# 1P3W.net
KiCad netlist of a schematic drawn in EAGLE
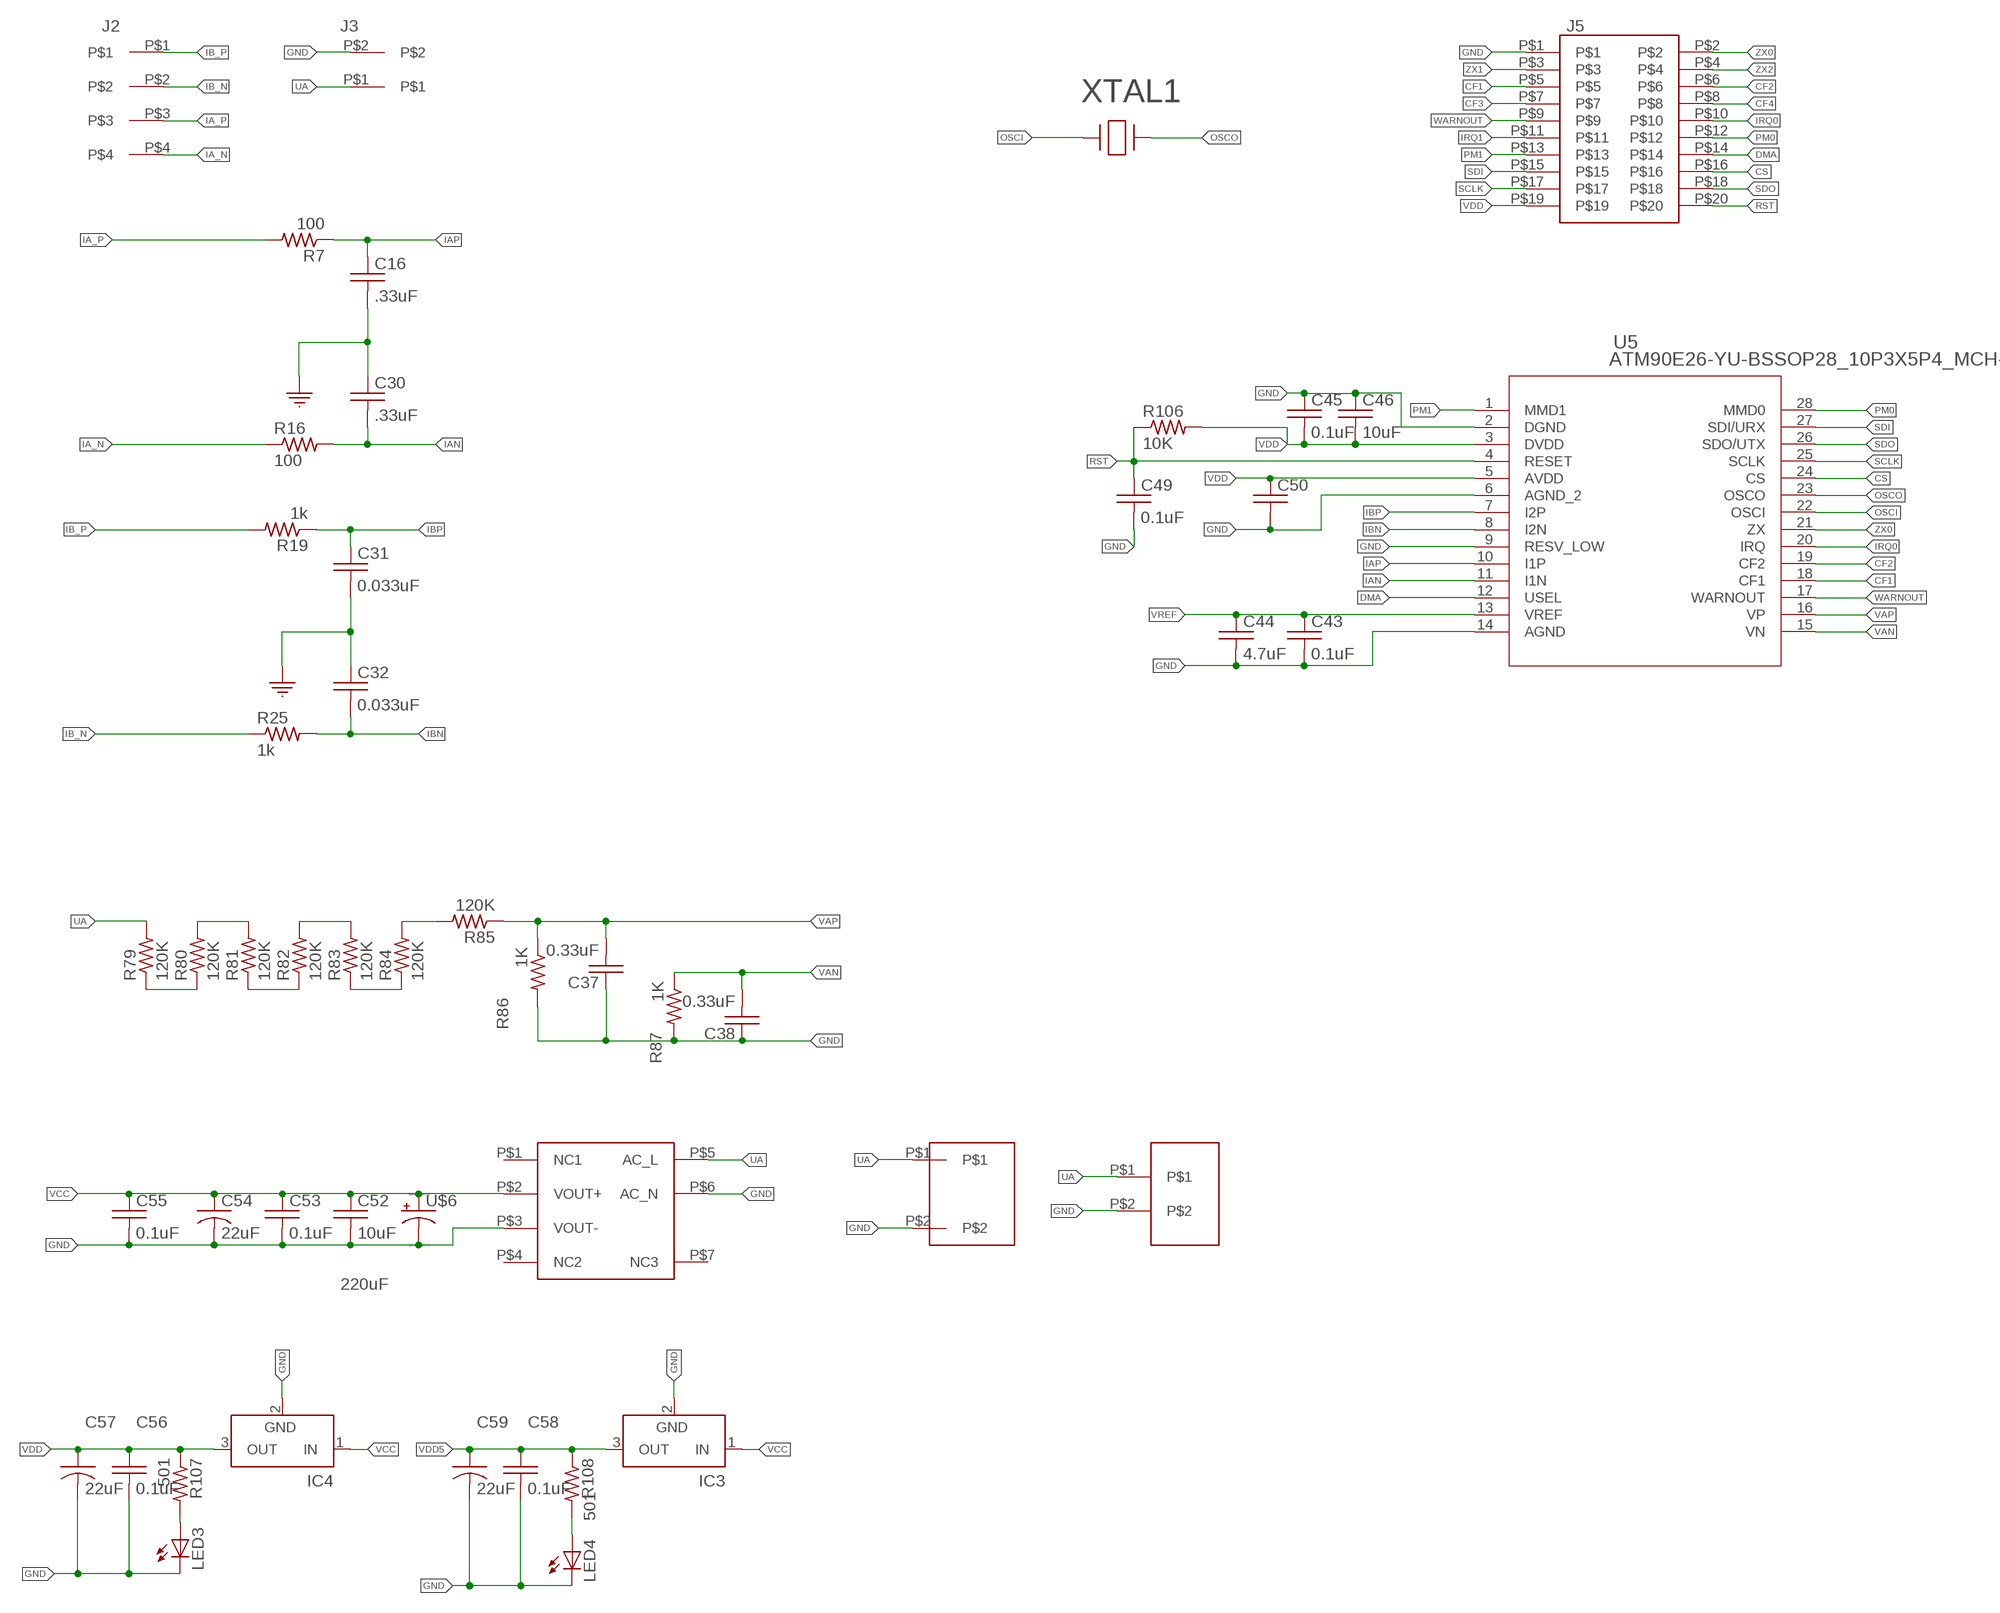
[diagram p0: schematic, sheet 1]

(export (version "E")
  (design (tool "Eeschema 10.0.6"))
  (components
    (comp (ref "C16")
      (value ".33uF")
      (footprint "eagle-import:0402")
      (libsource (lib "eagle-import") (part "C_0402"))
    )
    (comp (ref "C30")
      (value ".33uF")
      (footprint "eagle-import:0402")
      (libsource (lib "eagle-import") (part "C_0402"))
    )
    (comp (ref "C31")
      (value "0.033uF")
      (footprint "eagle-import:0402")
      (libsource (lib "eagle-import") (part "C_0402"))
    )
    (comp (ref "C32")
      (value "0.033uF")
      (footprint "eagle-import:0402")
      (libsource (lib "eagle-import") (part "C_0402"))
    )
    (comp (ref "C37")
      (value "0.33uF")
      (footprint "eagle-import:0402")
      (libsource (lib "eagle-import") (part "C_0402"))
    )
    (comp (ref "C38")
      (value "0.33uF")
      (footprint "eagle-import:0402")
      (libsource (lib "eagle-import") (part "C_0402"))
    )
    (comp (ref "C43")
      (value "0.1uF")
      (footprint "eagle-import:0402")
      (libsource (lib "eagle-import") (part "C_0402"))
    )
    (comp (ref "C44")
      (value "4.7uF")
      (footprint "eagle-import:0402")
      (libsource (lib "eagle-import") (part "C_0402"))
    )
    (comp (ref "C45")
      (value "0.1uF")
      (footprint "eagle-import:0402")
      (libsource (lib "eagle-import") (part "C_0402"))
    )
    (comp (ref "C46")
      (value "10uF")
      (footprint "eagle-import:0402")
      (libsource (lib "eagle-import") (part "C_0402"))
    )
    (comp (ref "C49")
      (value "0.1uF")
      (footprint "eagle-import:0402")
      (libsource (lib "eagle-import") (part "C_0402"))
    )
    (comp (ref "C50")
      (value "C_0402")
      (footprint "eagle-import:0402")
      (libsource (lib "eagle-import") (part "C_0402"))
    )
    (comp (ref "C51")
      (value "CAP_THIN_FILM_TDK_32922CAP")
      (footprint "eagle-import:CAP_THIN_FILM_32922")
      (libsource (lib "eagle-import") (part "CAP_THIN_FILM_TDK_32922CAP"))
    )
    (comp (ref "C52")
      (value "10uF")
      (footprint "eagle-import:0402")
      (libsource (lib "eagle-import") (part "C_0402"))
    )
    (comp (ref "C53")
      (value "0.1uF")
      (footprint "eagle-import:0402")
      (libsource (lib "eagle-import") (part "C_0402"))
    )
    (comp (ref "C54")
      (value "22uF")
      (footprint "eagle-import:C1206")
      (libsource (lib "eagle-import") (part "C-USC1206"))
    )
    (comp (ref "C55")
      (value "0.1uF")
      (footprint "eagle-import:0402")
      (libsource (lib "eagle-import") (part "C_0402"))
    )
    (comp (ref "C56")
      (value "0.1uF")
      (footprint "eagle-import:0402")
      (libsource (lib "eagle-import") (part "C_0402"))
    )
    (comp (ref "C57")
      (value "22uF")
      (footprint "eagle-import:C1206")
      (libsource (lib "eagle-import") (part "C-USC1206"))
    )
    (comp (ref "C58")
      (value "0.1uF")
      (footprint "eagle-import:0402")
      (libsource (lib "eagle-import") (part "C_0402"))
    )
    (comp (ref "C59")
      (value "22uF")
      (footprint "eagle-import:C1206")
      (libsource (lib "eagle-import") (part "C-USC1206"))
    )
    (comp (ref "IC3")
      (value "LT1129CST5")
      (footprint "eagle-import:SOT223")
      (fields (field (name "MPN") "LT1129CST-5#PBF"))
      (libsource (lib "eagle-import") (part "LT1129CST5"))
    )
    (comp (ref "IC4")
      (value "LT1129CST3")
      (footprint "eagle-import:SOT223")
      (fields (field (name "MPN") "LT1129CST-5#PBF"))
      (libsource (lib "eagle-import") (part "LT1129CST3"))
    )
    (comp (ref "J2")
      (value "3.81MM_1_X_4_RT_ANGLE_PLUG_HEADER")
      (footprint "eagle-import:1X4_3.81MM_PITCH")
      (libsource (lib "eagle-import") (part "3.81MM_1_X_4_RT_ANGLE_PLUG_HEADER"))
    )
    (comp (ref "J3")
      (value "3.81MM_1_X_2_RT_ANGLE_PLUG_HEADER")
      (footprint "eagle-import:2_3.81MM_PITCH")
      (libsource (lib "eagle-import") (part "3.81MM_1_X_2_RT_ANGLE_PLUG_HEADER"))
    )
    (comp (ref "J5")
      (value "2_X_10_HEADER_GENERIC")
      (footprint "eagle-import:2_X_10_.1_INCH")
      (libsource (lib "eagle-import") (part "2_X_10_HEADER_GENERIC"))
    )
    (comp (ref "LED3")
      (value "LED_0805_GREEN")
      (footprint "eagle-import:LED_0805_GREEN")
      (libsource (lib "eagle-import") (part "LED_0805_GREEN"))
    )
    (comp (ref "LED4")
      (value "LED_0805_GREEN")
      (footprint "eagle-import:LED_0805_GREEN")
      (libsource (lib "eagle-import") (part "LED_0805_GREEN"))
    )
    (comp (ref "R7")
      (value "100")
      (footprint "eagle-import:0402")
      (libsource (lib "eagle-import") (part "R_0402"))
    )
    (comp (ref "R16")
      (value "100")
      (footprint "eagle-import:0402")
      (libsource (lib "eagle-import") (part "R_0402"))
    )
    (comp (ref "R19")
      (value "1k")
      (footprint "eagle-import:0402")
      (libsource (lib "eagle-import") (part "R_0402"))
    )
    (comp (ref "R25")
      (value "1k")
      (footprint "eagle-import:0402")
      (libsource (lib "eagle-import") (part "R_0402"))
    )
    (comp (ref "R79")
      (value "120K")
      (footprint "eagle-import:0402")
      (libsource (lib "eagle-import") (part "R_0402"))
    )
    (comp (ref "R80")
      (value "120K")
      (footprint "eagle-import:0402")
      (libsource (lib "eagle-import") (part "R_0402"))
    )
    (comp (ref "R81")
      (value "120K")
      (footprint "eagle-import:0402")
      (libsource (lib "eagle-import") (part "R_0402"))
    )
    (comp (ref "R82")
      (value "120K")
      (footprint "eagle-import:0402")
      (libsource (lib "eagle-import") (part "R_0402"))
    )
    (comp (ref "R83")
      (value "120K")
      (footprint "eagle-import:0402")
      (libsource (lib "eagle-import") (part "R_0402"))
    )
    (comp (ref "R84")
      (value "120K")
      (footprint "eagle-import:0402")
      (libsource (lib "eagle-import") (part "R_0402"))
    )
    (comp (ref "R85")
      (value "120K")
      (footprint "eagle-import:0402")
      (libsource (lib "eagle-import") (part "R_0402"))
    )
    (comp (ref "R86")
      (value "1K")
      (footprint "eagle-import:0402")
      (libsource (lib "eagle-import") (part "R_0402"))
    )
    (comp (ref "R87")
      (value "1K")
      (footprint "eagle-import:0402")
      (libsource (lib "eagle-import") (part "R_0402"))
    )
    (comp (ref "R106")
      (value "10K")
      (footprint "eagle-import:0402")
      (libsource (lib "eagle-import") (part "R_0402"))
    )
    (comp (ref "R107")
      (value "501")
      (footprint "eagle-import:0402")
      (libsource (lib "eagle-import") (part "R_0402"))
    )
    (comp (ref "R108")
      (value "501")
      (footprint "eagle-import:0402")
      (libsource (lib "eagle-import") (part "R_0402"))
    )
    (comp (ref "U$5")
      (value "VAR_10MM_VDRUS10")
      (footprint "eagle-import:VAR_10MM_VDRUS10")
      (libsource (lib "eagle-import") (part "VAR_10MM_VDRUS10"))
    )
    (comp (ref "U$6")
      (value "220uF")
      (footprint "eagle-import:C_AL_ELECTROLYTIC_SMD_220UF")
      (libsource (lib "eagle-import") (part "C_AL_ELECTROLYTIC_SMD_220UF"))
    )
    (comp (ref "U4")
      (value "TMLM_04109")
      (footprint "eagle-import:TMLM04")
      (libsource (lib "eagle-import") (part "TMLM_04109"))
    )
    (comp (ref "U5")
      (value "ATM90E26-YU-BSSOP28_10P3X5P4_MCH-M")
      (footprint "eagle-import:SSOP28_10P3X5P4_MCH-M")
      (fields
        (field (name "MANUFACTURER_PART_NUMBER") "ATM90E26-YU-B")
        (field (name "COPYRIGHT") "Copyright (C) 2018 Accelerated Designs. All rights reserved")
      )
      (libsource (lib "eagle-import") (part "ATM90E26-YU-BSSOP28_10P3X5P4_MCH-M"))
    )
    (comp (ref "XTAL1")
      (value "ABLS-8.192MHZ-B2-TXTAL_HC/49US_ABLS_ABR-M")
      (footprint "eagle-import:XTAL_HC_49US_ABLS_ABR-M")
      (fields
        (field (name "MANUFACTURER_PART_NUMBER") "ABLS-8.192MHZ-B2-T")
        (field (name "COPYRIGHT") "Copyright (C) 2018 Accelerated Designs. All rights reserved")
      )
      (libsource (lib "eagle-import") (part "ABLS-8.192MHZ-B2-TXTAL_HC/49US_ABLS_ABR-M"))
    )
  )
  (nets
    (net (code "1") (name "CF1") (class "Default")
      (node (ref "J5") (pin "P$5") (pinfunction "P$5_P$5") (pintype "bidirectional"))
      (node (ref "U5") (pin "18") (pinfunction "CF1_18") (pintype "bidirectional"))
    )
    (net (code "2") (name "CF2") (class "Default")
      (node (ref "J5") (pin "P$6") (pinfunction "P$6_P$6") (pintype "bidirectional"))
      (node (ref "U5") (pin "19") (pinfunction "CF2_19") (pintype "bidirectional"))
    )
    (net (code "3") (name "CF3") (class "Default")
      (node (ref "J5") (pin "P$7") (pinfunction "P$7_P$7") (pintype "bidirectional"))
    )
    (net (code "4") (name "CF4") (class "Default")
      (node (ref "J5") (pin "P$8") (pinfunction "P$8_P$8") (pintype "bidirectional"))
    )
    (net (code "5") (name "CS") (class "Default")
      (node (ref "J5") (pin "P$16") (pinfunction "P$16_P$16") (pintype "bidirectional"))
      (node (ref "U5") (pin "24") (pinfunction "CS_24") (pintype "passive"))
    )
    (net (code "6") (name "DMA") (class "Default")
      (node (ref "J5") (pin "P$14") (pinfunction "P$14_P$14") (pintype "bidirectional"))
      (node (ref "U5") (pin "12") (pinfunction "USEL_12") (pintype "passive"))
    )
    (net (code "7") (name "GND") (class "Default")
      (node (ref "C16") (pin "P$2") (pinfunction "2_P$2") (pintype "passive"))
      (node (ref "C30") (pin "P$1") (pinfunction "1_P$1") (pintype "passive"))
      (node (ref "C31") (pin "P$2") (pinfunction "2_P$2") (pintype "passive"))
      (node (ref "C32") (pin "P$1") (pinfunction "1_P$1") (pintype "passive"))
      (node (ref "C37") (pin "P$1") (pinfunction "1_P$1") (pintype "passive"))
      (node (ref "C38") (pin "P$1") (pinfunction "1_P$1") (pintype "passive"))
      (node (ref "C43") (pin "P$2") (pinfunction "2_P$2") (pintype "passive"))
      (node (ref "C44") (pin "P$2") (pinfunction "2_P$2") (pintype "passive"))
      (node (ref "C45") (pin "P$1") (pinfunction "1_P$1") (pintype "passive"))
      (node (ref "C46") (pin "P$1") (pinfunction "1_P$1") (pintype "passive"))
      (node (ref "C49") (pin "P$2") (pinfunction "2_P$2") (pintype "passive"))
      (node (ref "C50") (pin "P$2") (pinfunction "2_P$2") (pintype "passive"))
      (node (ref "C51") (pin "P$2") (pinfunction "P$2_P$2") (pintype "bidirectional"))
      (node (ref "C52") (pin "P$2") (pinfunction "2_P$2") (pintype "passive"))
      (node (ref "C53") (pin "P$2") (pinfunction "2_P$2") (pintype "passive"))
      (node (ref "C54") (pin "2") (pinfunction "2_2") (pintype "passive"))
      (node (ref "C55") (pin "P$2") (pinfunction "2_P$2") (pintype "passive"))
      (node (ref "C56") (pin "P$2") (pinfunction "2_P$2") (pintype "passive"))
      (node (ref "C57") (pin "2") (pinfunction "2_2") (pintype "passive"))
      (node (ref "C58") (pin "P$2") (pinfunction "2_P$2") (pintype "passive"))
      (node (ref "C59") (pin "2") (pinfunction "2_2") (pintype "passive"))
      (node (ref "IC3") (pin "2") (pinfunction "GND_2") (pintype "power_in"))
      (node (ref "IC4") (pin "2") (pinfunction "GND_2") (pintype "power_in"))
      (node (ref "J3") (pin "P$2") (pinfunction "P$2_P$2") (pintype "bidirectional"))
      (node (ref "J5") (pin "P$1") (pinfunction "P$1_P$1") (pintype "bidirectional"))
      (node (ref "LED3") (pin "C") (pinfunction "C_C") (pintype "passive"))
      (node (ref "LED4") (pin "C") (pinfunction "C_C") (pintype "passive"))
      (node (ref "R86") (pin "P$2") (pinfunction "2_P$2") (pintype "passive"))
      (node (ref "R87") (pin "P$2") (pinfunction "2_P$2") (pintype "passive"))
      (node (ref "U$5") (pin "P$2") (pinfunction "P$2_P$2") (pintype "bidirectional"))
      (node (ref "U$6") (pin "N-") (pinfunction "-_N-") (pintype "passive"))
      (node (ref "U4") (pin "P$3") (pinfunction "VOUT-_P$3") (pintype "bidirectional"))
      (node (ref "U4") (pin "P$6") (pinfunction "AC_N_P$6") (pintype "bidirectional"))
      (node (ref "U5") (pin "14") (pinfunction "AGND_14") (pintype "passive"))
      (node (ref "U5") (pin "2") (pinfunction "DGND_2") (pintype "passive"))
      (node (ref "U5") (pin "6") (pinfunction "AGND_2_6") (pintype "passive"))
      (node (ref "U5") (pin "9") (pinfunction "RESV_LOW_9") (pintype "passive"))
    )
    (net (code "8") (name "IAN") (class "Default")
      (node (ref "C30") (pin "P$2") (pinfunction "2_P$2") (pintype "passive"))
      (node (ref "R16") (pin "P$2") (pinfunction "2_P$2") (pintype "passive"))
      (node (ref "U5") (pin "11") (pinfunction "I1N_11") (pintype "bidirectional"))
    )
    (net (code "9") (name "IAP") (class "Default")
      (node (ref "C16") (pin "P$1") (pinfunction "1_P$1") (pintype "passive"))
      (node (ref "R7") (pin "P$1") (pinfunction "1_P$1") (pintype "passive"))
      (node (ref "U5") (pin "10") (pinfunction "I1P_10") (pintype "bidirectional"))
    )
    (net (code "10") (name "IA_N") (class "Default")
      (node (ref "J2") (pin "P$4") (pinfunction "P$4_P$4") (pintype "bidirectional"))
      (node (ref "R16") (pin "P$1") (pinfunction "1_P$1") (pintype "passive"))
    )
    (net (code "11") (name "IA_P") (class "Default")
      (node (ref "J2") (pin "P$3") (pinfunction "P$3_P$3") (pintype "bidirectional"))
      (node (ref "R7") (pin "P$2") (pinfunction "2_P$2") (pintype "passive"))
    )
    (net (code "12") (name "IBN") (class "Default")
      (node (ref "C32") (pin "P$2") (pinfunction "2_P$2") (pintype "passive"))
      (node (ref "R25") (pin "P$2") (pinfunction "2_P$2") (pintype "passive"))
      (node (ref "U5") (pin "8") (pinfunction "I2N_8") (pintype "bidirectional"))
    )
    (net (code "13") (name "IBP") (class "Default")
      (node (ref "C31") (pin "P$1") (pinfunction "1_P$1") (pintype "passive"))
      (node (ref "R19") (pin "P$1") (pinfunction "1_P$1") (pintype "passive"))
      (node (ref "U5") (pin "7") (pinfunction "I2P_7") (pintype "bidirectional"))
    )
    (net (code "14") (name "IB_N") (class "Default")
      (node (ref "J2") (pin "P$2") (pinfunction "P$2_P$2") (pintype "bidirectional"))
      (node (ref "R25") (pin "P$1") (pinfunction "1_P$1") (pintype "passive"))
    )
    (net (code "15") (name "IB_P") (class "Default")
      (node (ref "J2") (pin "P$1") (pinfunction "P$1_P$1") (pintype "bidirectional"))
      (node (ref "R19") (pin "P$2") (pinfunction "2_P$2") (pintype "passive"))
    )
    (net (code "16") (name "IRQ0") (class "Default")
      (node (ref "J5") (pin "P$10") (pinfunction "P$10_P$10") (pintype "bidirectional"))
      (node (ref "U5") (pin "20") (pinfunction "IRQ_20") (pintype "passive"))
    )
    (net (code "17") (name "IRQ1") (class "Default")
      (node (ref "J5") (pin "P$11") (pinfunction "P$11_P$11") (pintype "bidirectional"))
    )
    (net (code "18") (name "Net-(R79-1)") (class "Default")
      (node (ref "R79") (pin "P$1") (pinfunction "1_P$1") (pintype "passive"))
      (node (ref "R80") (pin "P$1") (pinfunction "1_P$1") (pintype "passive"))
    )
    (net (code "19") (name "Net-(R80-2)") (class "Default")
      (node (ref "R80") (pin "P$2") (pinfunction "2_P$2") (pintype "passive"))
      (node (ref "R81") (pin "P$2") (pinfunction "2_P$2") (pintype "passive"))
    )
    (net (code "20") (name "Net-(R81-1)") (class "Default")
      (node (ref "R81") (pin "P$1") (pinfunction "1_P$1") (pintype "passive"))
      (node (ref "R82") (pin "P$1") (pinfunction "1_P$1") (pintype "passive"))
    )
    (net (code "21") (name "Net-(R82-2)") (class "Default")
      (node (ref "R82") (pin "P$2") (pinfunction "2_P$2") (pintype "passive"))
      (node (ref "R83") (pin "P$2") (pinfunction "2_P$2") (pintype "passive"))
    )
    (net (code "22") (name "Net-(R83-1)") (class "Default")
      (node (ref "R83") (pin "P$1") (pinfunction "1_P$1") (pintype "passive"))
      (node (ref "R84") (pin "P$1") (pinfunction "1_P$1") (pintype "passive"))
    )
    (net (code "23") (name "Net-(R84-2)") (class "Default")
      (node (ref "R84") (pin "P$2") (pinfunction "2_P$2") (pintype "passive"))
      (node (ref "R85") (pin "P$2") (pinfunction "2_P$2") (pintype "passive"))
    )
    (net (code "24") (name "Net-(R107-2)") (class "Default")
      (node (ref "LED3") (pin "A") (pinfunction "A_A") (pintype "passive"))
      (node (ref "R107") (pin "P$2") (pinfunction "2_P$2") (pintype "passive"))
    )
    (net (code "25") (name "Net-(R108-2)") (class "Default")
      (node (ref "LED4") (pin "A") (pinfunction "A_A") (pintype "passive"))
      (node (ref "R108") (pin "P$2") (pinfunction "2_P$2") (pintype "passive"))
    )
    (net (code "26") (name "OSCI") (class "Default")
      (node (ref "U5") (pin "22") (pinfunction "OSCI_22") (pintype "passive"))
      (node (ref "XTAL1") (pin "1") (pinfunction "1_1") (pintype "passive"))
    )
    (net (code "27") (name "OSCO") (class "Default")
      (node (ref "U5") (pin "23") (pinfunction "OSCO_23") (pintype "passive"))
      (node (ref "XTAL1") (pin "2") (pinfunction "2_2") (pintype "passive"))
    )
    (net (code "28") (name "PM0") (class "Default")
      (node (ref "J5") (pin "P$12") (pinfunction "P$12_P$12") (pintype "bidirectional"))
      (node (ref "U5") (pin "28") (pinfunction "MMD0_28") (pintype "bidirectional"))
    )
    (net (code "29") (name "PM1") (class "Default")
      (node (ref "J5") (pin "P$13") (pinfunction "P$13_P$13") (pintype "bidirectional"))
      (node (ref "U5") (pin "1") (pinfunction "MMD1_1") (pintype "bidirectional"))
    )
    (net (code "30") (name "RST") (class "Default")
      (node (ref "C49") (pin "P$1") (pinfunction "1_P$1") (pintype "passive"))
      (node (ref "J5") (pin "P$20") (pinfunction "P$20_P$20") (pintype "bidirectional"))
      (node (ref "R106") (pin "P$1") (pinfunction "1_P$1") (pintype "passive"))
      (node (ref "U5") (pin "4") (pinfunction "RESET_4") (pintype "passive"))
    )
    (net (code "31") (name "SCLK") (class "Default")
      (node (ref "J5") (pin "P$17") (pinfunction "P$17_P$17") (pintype "bidirectional"))
      (node (ref "U5") (pin "25") (pinfunction "SCLK_25") (pintype "passive"))
    )
    (net (code "32") (name "SDI") (class "Default")
      (node (ref "J5") (pin "P$15") (pinfunction "P$15_P$15") (pintype "bidirectional"))
      (node (ref "U5") (pin "27") (pinfunction "SDI/URX_27") (pintype "passive"))
    )
    (net (code "33") (name "SDO") (class "Default")
      (node (ref "J5") (pin "P$18") (pinfunction "P$18_P$18") (pintype "bidirectional"))
      (node (ref "U5") (pin "26") (pinfunction "SDO/UTX_26") (pintype "passive"))
    )
    (net (code "34") (name "UA") (class "Default")
      (node (ref "C51") (pin "P$1") (pinfunction "P$1_P$1") (pintype "bidirectional"))
      (node (ref "J3") (pin "P$1") (pinfunction "P$1_P$1") (pintype "bidirectional"))
      (node (ref "R79") (pin "P$2") (pinfunction "2_P$2") (pintype "passive"))
      (node (ref "U$5") (pin "P$1") (pinfunction "P$1_P$1") (pintype "bidirectional"))
      (node (ref "U4") (pin "P$5") (pinfunction "AC_L_P$5") (pintype "bidirectional"))
    )
    (net (code "35") (name "VAN") (class "Default")
      (node (ref "C38") (pin "P$2") (pinfunction "2_P$2") (pintype "passive"))
      (node (ref "R87") (pin "P$1") (pinfunction "1_P$1") (pintype "passive"))
      (node (ref "U5") (pin "15") (pinfunction "VN_15") (pintype "passive"))
    )
    (net (code "36") (name "VAP") (class "Default")
      (node (ref "C37") (pin "P$2") (pinfunction "2_P$2") (pintype "passive"))
      (node (ref "R85") (pin "P$1") (pinfunction "1_P$1") (pintype "passive"))
      (node (ref "R86") (pin "P$1") (pinfunction "1_P$1") (pintype "passive"))
      (node (ref "U5") (pin "16") (pinfunction "VP_16") (pintype "passive"))
    )
    (net (code "37") (name "VCC") (class "Default")
      (node (ref "C52") (pin "P$1") (pinfunction "1_P$1") (pintype "passive"))
      (node (ref "C53") (pin "P$1") (pinfunction "1_P$1") (pintype "passive"))
      (node (ref "C54") (pin "1") (pinfunction "1_1") (pintype "passive"))
      (node (ref "C55") (pin "P$1") (pinfunction "1_P$1") (pintype "passive"))
      (node (ref "IC3") (pin "1") (pinfunction "IN_1") (pintype "input"))
      (node (ref "IC4") (pin "1") (pinfunction "IN_1") (pintype "input"))
      (node (ref "U$6") (pin "P+") (pinfunction "+_P+") (pintype "passive"))
      (node (ref "U4") (pin "P$2") (pinfunction "VOUT+_P$2") (pintype "bidirectional"))
    )
    (net (code "38") (name "VDD") (class "Default")
      (node (ref "C45") (pin "P$2") (pinfunction "2_P$2") (pintype "passive"))
      (node (ref "C46") (pin "P$2") (pinfunction "2_P$2") (pintype "passive"))
      (node (ref "C50") (pin "P$1") (pinfunction "1_P$1") (pintype "passive"))
      (node (ref "C56") (pin "P$1") (pinfunction "1_P$1") (pintype "passive"))
      (node (ref "C57") (pin "1") (pinfunction "1_1") (pintype "passive"))
      (node (ref "IC4") (pin "3") (pinfunction "OUT_3") (pintype "output"))
      (node (ref "J5") (pin "P$19") (pinfunction "P$19_P$19") (pintype "bidirectional"))
      (node (ref "R106") (pin "P$2") (pinfunction "2_P$2") (pintype "passive"))
      (node (ref "R107") (pin "P$1") (pinfunction "1_P$1") (pintype "passive"))
      (node (ref "U5") (pin "3") (pinfunction "DVDD_3") (pintype "power_in"))
      (node (ref "U5") (pin "5") (pinfunction "AVDD_5") (pintype "power_in"))
    )
    (net (code "39") (name "VDD5") (class "Default")
      (node (ref "C58") (pin "P$1") (pinfunction "1_P$1") (pintype "passive"))
      (node (ref "C59") (pin "1") (pinfunction "1_1") (pintype "passive"))
      (node (ref "IC3") (pin "3") (pinfunction "OUT_3") (pintype "output"))
      (node (ref "R108") (pin "P$1") (pinfunction "1_P$1") (pintype "passive"))
    )
    (net (code "40") (name "VREF") (class "Default")
      (node (ref "C43") (pin "P$1") (pinfunction "1_P$1") (pintype "passive"))
      (node (ref "C44") (pin "P$1") (pinfunction "1_P$1") (pintype "passive"))
      (node (ref "U5") (pin "13") (pinfunction "VREF_13") (pintype "power_in"))
    )
    (net (code "41") (name "WARNOUT") (class "Default")
      (node (ref "J5") (pin "P$9") (pinfunction "P$9_P$9") (pintype "bidirectional"))
      (node (ref "U5") (pin "17") (pinfunction "WARNOUT_17") (pintype "output"))
    )
    (net (code "42") (name "ZX0") (class "Default")
      (node (ref "J5") (pin "P$2") (pinfunction "P$2_P$2") (pintype "bidirectional"))
      (node (ref "U5") (pin "21") (pinfunction "ZX_21") (pintype "passive"))
    )
    (net (code "43") (name "ZX1") (class "Default")
      (node (ref "J5") (pin "P$3") (pinfunction "P$3_P$3") (pintype "bidirectional"))
    )
    (net (code "44") (name "ZX2") (class "Default")
      (node (ref "J5") (pin "P$4") (pinfunction "P$4_P$4") (pintype "bidirectional"))
    )
    (net (code "45") (name "unconnected-(U4-NC1-PadP$1)") (class "Default")
      (node (ref "U4") (pin "P$1") (pinfunction "NC1_P$1") (pintype "bidirectional"))
    )
    (net (code "46") (name "unconnected-(U4-NC2-PadP$4)") (class "Default")
      (node (ref "U4") (pin "P$4") (pinfunction "NC2_P$4") (pintype "bidirectional"))
    )
    (net (code "47") (name "unconnected-(U4-NC3-PadP$7)") (class "Default")
      (node (ref "U4") (pin "P$7") (pinfunction "NC3_P$7") (pintype "bidirectional"))
    )
  )
)
